# USBPD_Sink.net
KiCad netlist of a schematic drawn in Altium Designer
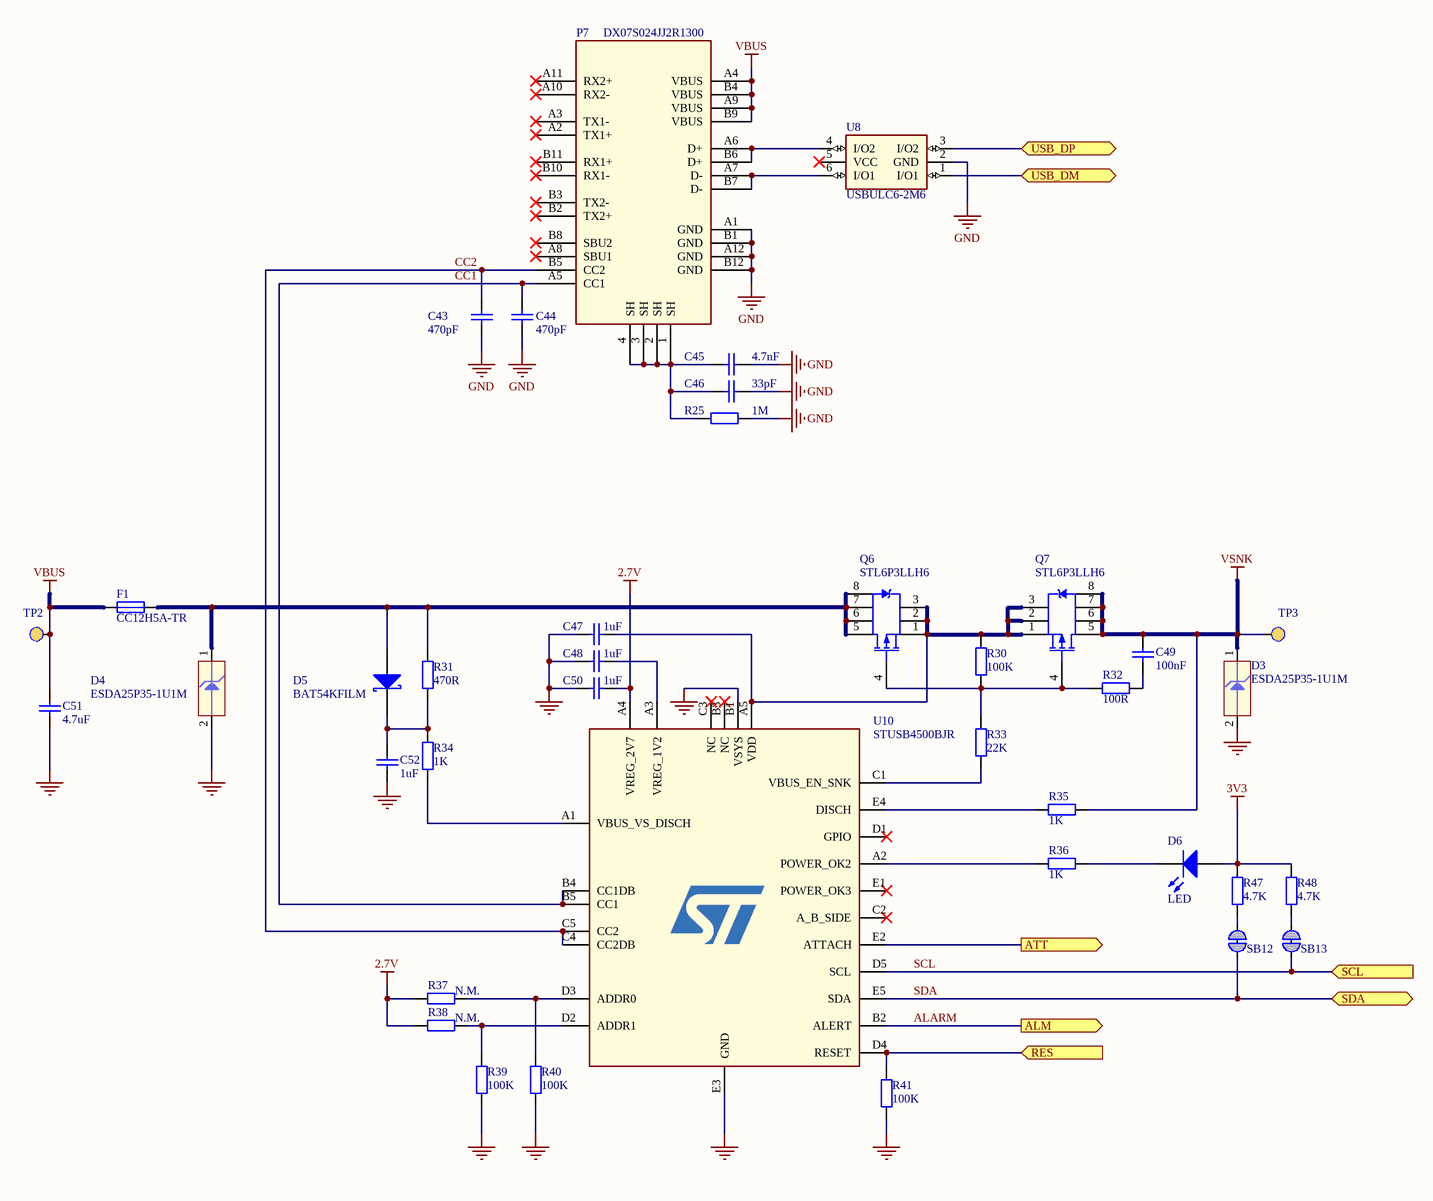
[diagram p0: USBPD_Sink.SchDoc]

(export (version "E")
  (design (tool "Eeschema 10.0.6"))
  (components
    (comp (ref "C43")
      (value "470pF")
      (footprint "C0402")
      (description "Capacitor (Semiconductor SIM Model)")
      (fields
        (field (name "MANUFACTURER") "Samsung EM")
        (field (name "MANUFACTURER PART NO.") "CL05C471JB5NNNC")
      )
      (libsource (lib "Miscellaneous Devices") (part "Cap Semi"))
    )
    (comp (ref "C44")
      (value "470pF")
      (footprint "C0402")
      (description "Capacitor (Semiconductor SIM Model)")
      (fields
        (field (name "MANUFACTURER") "Samsung EM")
        (field (name "MANUFACTURER PART NO.") "CL05C471JB5NNNC")
      )
      (libsource (lib "Miscellaneous Devices") (part "Cap Semi"))
    )
    (comp (ref "C45")
      (value "4.7nF")
      (footprint "C0402")
      (description "Capacitor (Semiconductor SIM Model)")
      (fields
        (field (name "MANUFACTURER") "YAGEO")
        (field (name "MANUFACTURER PART NO.") "CC0402KRX7R9BB472")
      )
      (libsource (lib "Miscellaneous Devices") (part "Cap Semi"))
    )
    (comp (ref "C46")
      (value "33pF")
      (footprint "C0402")
      (description "Capacitor (Semiconductor SIM Model)")
      (fields (field (name "MANUFACTURER") "AVX") (field (name "MANUFACTURER PART NO.") "04025A330JAT2A"))
      (libsource (lib "Miscellaneous Devices") (part "Cap Semi"))
    )
    (comp (ref "C47")
      (value "1uF")
      (footprint "C0402")
      (description "Capacitor (Semiconductor SIM Model)")
      (fields
        (field (name "MANUFACTURER") "muRata")
        (field (name "MANUFACTURER PART NO.") "GRM155R61E105KA12D")
      )
      (libsource (lib "Miscellaneous Devices") (part "Cap Semi"))
    )
    (comp (ref "C48")
      (value "1uF")
      (footprint "C0402")
      (description "Capacitor (Semiconductor SIM Model)")
      (fields
        (field (name "MANUFACTURER") "muRata")
        (field (name "MANUFACTURER PART NO.") "GRM155R61E105KA12D")
      )
      (libsource (lib "Miscellaneous Devices") (part "Cap Semi"))
    )
    (comp (ref "C49")
      (value "100nF")
      (footprint "C0402")
      (description "Capacitor (Semiconductor SIM Model)")
      (fields
        (field (name "MANUFACTURER") "YAGEO")
        (field (name "MANUFACTURER PART NO.") "CC0402KRX7R9BB104")
      )
      (libsource (lib "Miscellaneous Devices") (part "Cap Semi"))
    )
    (comp (ref "C50")
      (value "1uF")
      (footprint "C0402")
      (description "Capacitor (Semiconductor SIM Model)")
      (fields
        (field (name "MANUFACTURER") "muRata")
        (field (name "MANUFACTURER PART NO.") "GRM155R61E105KA12D")
      )
      (libsource (lib "Miscellaneous Devices") (part "Cap Semi"))
    )
    (comp (ref "C51")
      (value "4.7uF")
      (footprint "C0603")
      (description "Capacitor (Semiconductor SIM Model)")
      (fields
        (field (name "MANUFACTURER") "Samsung EM")
        (field (name "MANUFACTURER PART NO.") "CL10A475KA8NQNC")
      )
      (libsource (lib "Miscellaneous Devices") (part "Cap Semi"))
    )
    (comp (ref "C52")
      (value "1uF")
      (footprint "C0402")
      (description "Capacitor (Semiconductor SIM Model)")
      (fields
        (field (name "MANUFACTURER") "muRata")
        (field (name "MANUFACTURER PART NO.") "GRM155R61E105KA12D")
      )
      (libsource (lib "Miscellaneous Devices") (part "Cap Semi"))
    )
    (comp (ref "D3")
      (value "ESDA25P35-1U1M")
      (footprint "QFN1610")
      (description "ESD Diode Symbol")
      (fields (field (name "MANUFACTURER") "STMicroelectronics"))
      (libsource (lib "ESD_Diode") (part "ESD_Diode"))
    )
    (comp (ref "D4")
      (value "ESDA25P35-1U1M")
      (footprint "QFN1610")
      (description "ESD Diode Symbol")
      (fields (field (name "MANUFACTURER") "STMicroelectronics"))
      (libsource (lib "ESD_Diode") (part "ESD_Diode"))
    )
    (comp (ref "D5")
      (value "BAT54KFILM")
      (footprint "SOD-523")
      (description "Schottky Diode")
      (fields (field (name "MANUFACTURER") "STMicroelectronics"))
      (libsource (lib "Miscellaneous Devices") (part "D Schottky"))
    )
    (comp (ref "D6")
      (value "LED")
      (footprint "PICOLED")
      (description "Typical SMD LED")
      (fields
        (field (name "MANUFACTURER") "OSRAM")
        (field (name "MANUFACTURER PART NO.") "LTQH9G-Q2OO-25-2Z4Y-5-R18")
      )
      (libsource (lib "Miscellaneous Devices") (part "LED2"))
    )
    (comp (ref "F1")
      (value "CC12H5A-TR")
      (footprint "R1206")
      (description "Fuse")
      (fields (field (name "MANUFACTURER") "EATON"))
      (libsource (lib "DevKit_STM32L5") (part "Fuse"))
    )
    (comp (ref "P7")
      (value "DX07S024JJ2R1300")
      (footprint "DX07_USB_C")
      (description "24P USB C DUAL SMT ON BOARD")
      (fields (field (name "MANUFACTURER") "JAE"))
      (libsource (lib "DX07S024JJ2R1300") (part "DX07S024JJ2R1300"))
    )
    (comp (ref "Q6")
      (value "STL6P3LLH6")
      (footprint "PowerFLAT™ 3.3 x 3.3")
      (description "Power MOSFET")
      (fields (field (name "MANUFACTURER") "STMicroelectronics"))
      (libsource (lib "RUT_GE310_GNSS") (part "STL6P3LLH6"))
    )
    (comp (ref "Q7")
      (value "STL6P3LLH6")
      (footprint "PowerFLAT™ 3.3 x 3.3")
      (description "Power MOSFET")
      (fields (field (name "MANUFACTURER") "STMicroelectronics"))
      (libsource (lib "RUT_GE310_GNSS") (part "STL6P3LLH6"))
    )
    (comp (ref "R25")
      (value "1M")
      (footprint "R0402")
      (fields
        (field (name "MANUFACTURER") "ASJ")
        (field (name "MANUFACTURER PART NO.") "CR10-105-JK")
        (field (name "Comment") "Res2")
      )
      (libsource (lib "Miscellaneous Devices") (part "Res2"))
    )
    (comp (ref "R30")
      (value "100K")
      (footprint "R0402")
      (fields
        (field (name "MANUFACTURER") "ASJ")
        (field (name "MANUFACTURER PART NO.") "CR10-104-JN")
        (field (name "Comment") "Res2")
      )
      (libsource (lib "Miscellaneous Devices") (part "Res2"))
    )
    (comp (ref "R31")
      (value "470R")
      (footprint "R0402")
      (fields
        (field (name "MANUFACTURER") "ASJ")
        (field (name "MANUFACTURER PART NO.") "CR10-471-JK")
        (field (name "Comment") "Res2")
      )
      (libsource (lib "Miscellaneous Devices") (part "Res2"))
    )
    (comp (ref "R32")
      (value "100R")
      (footprint "R0402")
      (fields
        (field (name "MANUFACTURER") "YAGEO")
        (field (name "MANUFACTURER PART NO.") "RC0402JR-07100RL")
        (field (name "Comment") "Res2")
      )
      (libsource (lib "") (part "Res2_1"))
    )
    (comp (ref "R33")
      (value "22K")
      (footprint "R0402")
      (fields
        (field (name "MANUFACTURER") "ASJ")
        (field (name "MANUFACTURER PART NO.") "CR10-223-JK")
        (field (name "Comment") "Res2")
      )
      (libsource (lib "Miscellaneous Devices") (part "Res2"))
    )
    (comp (ref "R34")
      (value "1K")
      (footprint "R0402")
      (fields
        (field (name "MANUFACTURER") "ASJ")
        (field (name "MANUFACTURER PART NO.") "CR10-102-JK")
        (field (name "Comment") "Res2")
      )
      (libsource (lib "Miscellaneous Devices") (part "Res2"))
    )
    (comp (ref "R35")
      (value "1K")
      (footprint "R0402")
      (fields
        (field (name "MANUFACTURER") "ASJ")
        (field (name "MANUFACTURER PART NO.") "CR10-102-JK")
        (field (name "Comment") "Res2")
      )
      (libsource (lib "") (part "Res2_1"))
    )
    (comp (ref "R36")
      (value "1K")
      (footprint "R0402")
      (fields
        (field (name "MANUFACTURER") "ASJ")
        (field (name "MANUFACTURER PART NO.") "CR10-102-JK")
        (field (name "Comment") "Res2")
      )
      (libsource (lib "") (part "Res2_1"))
    )
    (comp (ref "R37")
      (value "N.M.")
      (footprint "R0402")
      (fields
        (field (name "MANUFACTURER") "Yageo")
        (field (name "MANUFACTURER PART NO.") "RC0402JR-0710KL")
        (field (name "Comment") "Res2")
      )
      (libsource (lib "") (part "Res2_1"))
    )
    (comp (ref "R38")
      (value "N.M.")
      (footprint "R0402")
      (fields
        (field (name "MANUFACTURER") "Yageo")
        (field (name "MANUFACTURER PART NO.") "RC0402JR-0710KL")
        (field (name "Comment") "Res2")
      )
      (libsource (lib "") (part "Res2_1"))
    )
    (comp (ref "R39")
      (value "100K")
      (footprint "R0402")
      (fields
        (field (name "MANUFACTURER") "ASJ")
        (field (name "MANUFACTURER PART NO.") "CR10-104-JN")
        (field (name "Comment") "Res2")
      )
      (libsource (lib "Miscellaneous Devices") (part "Res2"))
    )
    (comp (ref "R40")
      (value "100K")
      (footprint "R0402")
      (fields
        (field (name "MANUFACTURER") "ASJ")
        (field (name "MANUFACTURER PART NO.") "CR10-104-JN")
        (field (name "Comment") "Res2")
      )
      (libsource (lib "Miscellaneous Devices") (part "Res2"))
    )
    (comp (ref "R41")
      (value "100K")
      (footprint "R0402")
      (fields
        (field (name "MANUFACTURER") "ASJ")
        (field (name "MANUFACTURER PART NO.") "CR10-104-JN")
        (field (name "Comment") "Res2")
      )
      (libsource (lib "Miscellaneous Devices") (part "Res2"))
    )
    (comp (ref "R47")
      (value "4.7K")
      (footprint "R0402")
      (fields
        (field (name "MANUFACTURER") "ASJ")
        (field (name "MANUFACTURER PART NO.") "CR10-472-JK")
        (field (name "Comment") "Res2")
      )
      (libsource (lib "Miscellaneous Devices") (part "Res2"))
    )
    (comp (ref "R48")
      (value "4.7K")
      (footprint "R0402")
      (fields
        (field (name "MANUFACTURER") "ASJ")
        (field (name "MANUFACTURER PART NO.") "CR10-472-JK")
        (field (name "Comment") "Res2")
      )
      (libsource (lib "Miscellaneous Devices") (part "Res2"))
    )
    (comp (ref "SB12")
      (value "Solderbridge")
      (footprint "Solderbridge_Shorted")
      (libsource (lib "altium-import") (part "root_1_SOLDERBRIDGE_SHORTED_"))
    )
    (comp (ref "SB13")
      (value "Solderbridge")
      (footprint "Solderbridge_Shorted")
      (libsource (lib "altium-import") (part "root_1_SOLDERBRIDGE_SHORTED_"))
    )
    (comp (ref "TP2")
      (value "Test_Point")
      (footprint "TEST_POINT")
      (description "Test Point")
      (libsource (lib "Test Point") (part "Test_Point"))
    )
    (comp (ref "TP3")
      (value "Test_Point")
      (footprint "TEST_POINT")
      (description "Test Point")
      (libsource (lib "Test Point") (part "Test_Point"))
    )
    (comp (ref "U8")
      (value "USBULC6-2M6")
      (footprint "Micro_QFN_6L")
      (description "Ultra large bandwidth ESD protection")
      (fields (field (name "MANUFACTURER") "STMicroelectronics"))
      (libsource (lib "USBULC6-2M6") (part "USBULC6-2M6"))
    )
    (comp (ref "U10")
      (value "STUSB4500BJR")
      (footprint "WLCSP 2.6x2.6x0.5")
      (description "Standalone USB PD sink controller with short-to-VBUS protections")
      (fields (field (name "MANUFACTURER") "STMicroelectronics"))
      (libsource (lib "STUSB4500BJR ") (part "STUSB4500BJR"))
    )
  )
  (nets
    (net (code "1") (name "/ALARM") (class "Default")
      (node (ref "U10") (pin "B2") (pinfunction "ALERT_B2") (pintype "passive"))
    )
    (net (code "2") (name "/ATT") (class "Default")
      (node (ref "U10") (pin "E2") (pinfunction "ATTACH_E2") (pintype "passive"))
    )
    (net (code "3") (name "/CC1") (class "Default")
      (node (ref "C44") (pin "2") (pinfunction "2_2") (pintype "passive"))
      (node (ref "P7") (pin "A5") (pinfunction "CC1_A5") (pintype "passive"))
      (node (ref "U10") (pin "B4") (pinfunction "CC1DB_B4") (pintype "passive"))
      (node (ref "U10") (pin "B5") (pinfunction "CC1_B5") (pintype "passive"))
    )
    (net (code "4") (name "/CC2") (class "Default")
      (node (ref "C43") (pin "2") (pinfunction "2_2") (pintype "passive"))
      (node (ref "P7") (pin "B5") (pinfunction "CC2_B5") (pintype "passive"))
      (node (ref "U10") (pin "C4") (pinfunction "CC2DB_C4") (pintype "passive"))
      (node (ref "U10") (pin "C5") (pinfunction "CC2_C5") (pintype "passive"))
    )
    (net (code "5") (name "/RES") (class "Default")
      (node (ref "R41") (pin "1") (pinfunction "1_1") (pintype "passive"))
      (node (ref "U10") (pin "D4") (pinfunction "RESET_D4") (pintype "passive"))
    )
    (net (code "6") (name "/SCL") (class "Default")
      (node (ref "SB13") (pin "2") (pinfunction "1_2") (pintype "passive"))
      (node (ref "U10") (pin "D5") (pinfunction "SCL_D5") (pintype "passive"))
    )
    (net (code "7") (name "/SDA") (class "Default")
      (node (ref "SB12") (pin "2") (pinfunction "1_2") (pintype "passive"))
      (node (ref "U10") (pin "E5") (pinfunction "SDA_E5") (pintype "passive"))
    )
    (net (code "8") (name "/USB_DM") (class "Default")
      (node (ref "U8") (pin "1") (pinfunction "I/O1_1") (pintype "bidirectional"))
    )
    (net (code "9") (name "/USB_DP") (class "Default")
      (node (ref "U8") (pin "3") (pinfunction "I/O2_3") (pintype "bidirectional"))
    )
    (net (code "10") (name "2.7V") (class "Default")
      (node (ref "C50") (pin "1") (pinfunction "1_1") (pintype "passive"))
      (node (ref "R37") (pin "1") (pinfunction "1_1") (pintype "passive"))
      (node (ref "R38") (pin "1") (pinfunction "1_1") (pintype "passive"))
      (node (ref "U10") (pin "A4") (pinfunction "VREG_2V7_A4") (pintype "passive"))
    )
    (net (code "11") (name "3V3") (class "Default")
      (node (ref "D6") (pin "1") (pinfunction "A_1") (pintype "passive"))
      (node (ref "R47") (pin "1") (pinfunction "1_1") (pintype "passive"))
      (node (ref "R48") (pin "1") (pinfunction "1_1") (pintype "passive"))
    )
    (net (code "12") (name "GND") (class "Default")
      (node (ref "C43") (pin "1") (pinfunction "1_1") (pintype "passive"))
      (node (ref "C44") (pin "1") (pinfunction "1_1") (pintype "passive"))
      (node (ref "C45") (pin "1") (pinfunction "1_1") (pintype "passive"))
      (node (ref "C46") (pin "1") (pinfunction "1_1") (pintype "passive"))
      (node (ref "C47") (pin "2") (pinfunction "2_2") (pintype "passive"))
      (node (ref "C48") (pin "2") (pinfunction "2_2") (pintype "passive"))
      (node (ref "C50") (pin "2") (pinfunction "2_2") (pintype "passive"))
      (node (ref "C51") (pin "2") (pinfunction "2_2") (pintype "passive"))
      (node (ref "C52") (pin "2") (pinfunction "2_2") (pintype "passive"))
      (node (ref "D3") (pin "2") (pinfunction "PIN2_2") (pintype "passive"))
      (node (ref "D4") (pin "2") (pinfunction "PIN2_2") (pintype "passive"))
      (node (ref "P7") (pin "A1") (pinfunction "GND_A1") (pintype "passive"))
      (node (ref "P7") (pin "A12") (pinfunction "GND_A12") (pintype "passive"))
      (node (ref "P7") (pin "B1") (pinfunction "GND_B1") (pintype "passive"))
      (node (ref "P7") (pin "B12") (pinfunction "GND_B12") (pintype "passive"))
      (node (ref "R25") (pin "1") (pinfunction "1_1") (pintype "passive"))
      (node (ref "R39") (pin "2") (pinfunction "2_2") (pintype "passive"))
      (node (ref "R40") (pin "2") (pinfunction "2_2") (pintype "passive"))
      (node (ref "R41") (pin "2") (pinfunction "2_2") (pintype "passive"))
      (node (ref "U10") (pin "B1") (pinfunction "VSYS_B1") (pintype "passive"))
      (node (ref "U10") (pin "E3") (pinfunction "GND_E3") (pintype "passive"))
      (node (ref "U8") (pin "2") (pinfunction "GND_2") (pintype "power_in"))
    )
    (net (code "13") (name "Net-(C45-Pad2)") (class "Default")
      (node (ref "C45") (pin "2") (pinfunction "2_2") (pintype "passive"))
      (node (ref "C46") (pin "2") (pinfunction "2_2") (pintype "passive"))
      (node (ref "P7") (pin "1") (pinfunction "SH_1") (pintype "passive"))
      (node (ref "P7") (pin "2") (pinfunction "SH_2") (pintype "passive"))
      (node (ref "P7") (pin "3") (pinfunction "SH_3") (pintype "passive"))
      (node (ref "P7") (pin "4") (pinfunction "SH_4") (pintype "passive"))
      (node (ref "R25") (pin "2") (pinfunction "2_2") (pintype "passive"))
    )
    (net (code "14") (name "Net-(C49-Pad1)") (class "Default")
      (node (ref "C49") (pin "1") (pinfunction "1_1") (pintype "passive"))
      (node (ref "R32") (pin "2") (pinfunction "2_2") (pintype "passive"))
    )
    (net (code "15") (name "Net-(D4-PIN1)") (class "Default")
      (node (ref "D4") (pin "1") (pinfunction "PIN1_1") (pintype "passive"))
      (node (ref "D5") (pin "1") (pinfunction "A_1") (pintype "passive"))
      (node (ref "F1") (pin "1") (pinfunction "1_1") (pintype "passive"))
      (node (ref "Q6") (pin "5") (pinfunction "D_5") (pintype "passive"))
      (node (ref "Q6") (pin "6") (pinfunction "D_6") (pintype "passive"))
      (node (ref "Q6") (pin "7") (pinfunction "D_7") (pintype "passive"))
      (node (ref "Q6") (pin "8") (pinfunction "D_8") (pintype "passive"))
      (node (ref "R31") (pin "1") (pinfunction "1_1") (pintype "passive"))
    )
    (net (code "16") (name "Net-(D5-K)") (class "Default")
      (node (ref "C52") (pin "1") (pinfunction "1_1") (pintype "passive"))
      (node (ref "D5") (pin "2") (pinfunction "K_2") (pintype "passive"))
      (node (ref "R31") (pin "2") (pinfunction "2_2") (pintype "passive"))
      (node (ref "R34") (pin "1") (pinfunction "1_1") (pintype "passive"))
    )
    (net (code "17") (name "Net-(D6-K)") (class "Default")
      (node (ref "D6") (pin "2") (pinfunction "K_2") (pintype "passive"))
      (node (ref "R36") (pin "2") (pinfunction "2_2") (pintype "passive"))
    )
    (net (code "18") (name "Net-(P7-D+-PadA6)") (class "Default")
      (node (ref "P7") (pin "A6") (pinfunction "D+_A6") (pintype "passive"))
      (node (ref "P7") (pin "B6") (pinfunction "D+_B6") (pintype "passive"))
      (node (ref "U8") (pin "4") (pinfunction "I/O2_4") (pintype "bidirectional"))
    )
    (net (code "19") (name "Net-(P7-D--PadA7)") (class "Default")
      (node (ref "P7") (pin "A7") (pinfunction "D-_A7") (pintype "passive"))
      (node (ref "P7") (pin "B7") (pinfunction "D-_B7") (pintype "passive"))
      (node (ref "U8") (pin "6") (pinfunction "I/O1_6") (pintype "bidirectional"))
    )
    (net (code "20") (name "Net-(Q6-G)") (class "Default")
      (node (ref "Q6") (pin "4") (pinfunction "G_4") (pintype "passive"))
      (node (ref "Q7") (pin "4") (pinfunction "G_4") (pintype "passive"))
      (node (ref "R30") (pin "2") (pinfunction "2_2") (pintype "passive"))
      (node (ref "R32") (pin "1") (pinfunction "1_1") (pintype "passive"))
      (node (ref "R33") (pin "1") (pinfunction "1_1") (pintype "passive"))
    )
    (net (code "21") (name "Net-(SB12-0)") (class "Default")
      (node (ref "R47") (pin "2") (pinfunction "2_2") (pintype "passive"))
      (node (ref "SB12") (pin "1") (pinfunction "0_1") (pintype "passive"))
    )
    (net (code "22") (name "Net-(SB13-0)") (class "Default")
      (node (ref "R48") (pin "2") (pinfunction "2_2") (pintype "passive"))
      (node (ref "SB13") (pin "1") (pinfunction "0_1") (pintype "passive"))
    )
    (net (code "23") (name "Net-(U10-ADDR0)") (class "Default")
      (node (ref "R37") (pin "2") (pinfunction "2_2") (pintype "passive"))
      (node (ref "R40") (pin "1") (pinfunction "1_1") (pintype "passive"))
      (node (ref "U10") (pin "D3") (pinfunction "ADDR0_D3") (pintype "passive"))
    )
    (net (code "24") (name "Net-(U10-ADDR1)") (class "Default")
      (node (ref "R38") (pin "2") (pinfunction "2_2") (pintype "passive"))
      (node (ref "R39") (pin "1") (pinfunction "1_1") (pintype "passive"))
      (node (ref "U10") (pin "D2") (pinfunction "ADDR1_D2") (pintype "passive"))
    )
    (net (code "25") (name "Net-(U10-DISCH)") (class "Default")
      (node (ref "R35") (pin "1") (pinfunction "1_1") (pintype "passive"))
      (node (ref "U10") (pin "E4") (pinfunction "DISCH_E4") (pintype "passive"))
    )
    (net (code "26") (name "Net-(U10-POWER_OK2)") (class "Default")
      (node (ref "R36") (pin "1") (pinfunction "1_1") (pintype "passive"))
      (node (ref "U10") (pin "A2") (pinfunction "POWER_OK2_A2") (pintype "passive"))
    )
    (net (code "27") (name "Net-(U10-VBUS_EN_SNK)") (class "Default")
      (node (ref "R33") (pin "2") (pinfunction "2_2") (pintype "passive"))
      (node (ref "U10") (pin "C1") (pinfunction "VBUS_EN_SNK_C1") (pintype "passive"))
    )
    (net (code "28") (name "Net-(U10-VBUS_VS_DISCH)") (class "Default")
      (node (ref "R34") (pin "2") (pinfunction "2_2") (pintype "passive"))
      (node (ref "U10") (pin "A1") (pinfunction "VBUS_VS_DISCH_A1") (pintype "passive"))
    )
    (net (code "29") (name "Net-(U10-VDD)") (class "Default")
      (node (ref "C47") (pin "1") (pinfunction "1_1") (pintype "passive"))
      (node (ref "Q6") (pin "1") (pinfunction "S_1") (pintype "passive"))
      (node (ref "Q6") (pin "2") (pinfunction "S_2") (pintype "passive"))
      (node (ref "Q6") (pin "3") (pinfunction "S_3") (pintype "passive"))
      (node (ref "Q7") (pin "1") (pinfunction "S_1") (pintype "passive"))
      (node (ref "Q7") (pin "2") (pinfunction "S_2") (pintype "passive"))
      (node (ref "Q7") (pin "3") (pinfunction "S_3") (pintype "passive"))
      (node (ref "R30") (pin "1") (pinfunction "1_1") (pintype "passive"))
      (node (ref "U10") (pin "A5") (pinfunction "VDD_A5") (pintype "passive"))
    )
    (net (code "30") (name "Net-(U10-VREG_1V2)") (class "Default")
      (node (ref "C48") (pin "1") (pinfunction "1_1") (pintype "passive"))
      (node (ref "U10") (pin "A3") (pinfunction "VREG_1V2_A3") (pintype "passive"))
    )
    (net (code "31") (name "VBUS") (class "Default")
      (node (ref "C51") (pin "1") (pinfunction "1_1") (pintype "passive"))
      (node (ref "F1") (pin "2") (pinfunction "2_2") (pintype "passive"))
      (node (ref "P7") (pin "A4") (pinfunction "VBUS_A4") (pintype "passive"))
      (node (ref "P7") (pin "A9") (pinfunction "VBUS_A9") (pintype "passive"))
      (node (ref "P7") (pin "B4") (pinfunction "VBUS_B4") (pintype "passive"))
      (node (ref "P7") (pin "B9") (pinfunction "VBUS_B9") (pintype "passive"))
      (node (ref "TP2") (pin "0") (pinfunction "0_0") (pintype "passive"))
    )
    (net (code "32") (name "VSNK") (class "Default")
      (node (ref "C49") (pin "2") (pinfunction "2_2") (pintype "passive"))
      (node (ref "D3") (pin "1") (pinfunction "PIN1_1") (pintype "passive"))
      (node (ref "Q7") (pin "5") (pinfunction "D_5") (pintype "passive"))
      (node (ref "Q7") (pin "6") (pinfunction "D_6") (pintype "passive"))
      (node (ref "Q7") (pin "7") (pinfunction "D_7") (pintype "passive"))
      (node (ref "Q7") (pin "8") (pinfunction "D_8") (pintype "passive"))
      (node (ref "R35") (pin "2") (pinfunction "2_2") (pintype "passive"))
      (node (ref "TP3") (pin "0") (pinfunction "0_0") (pintype "passive"))
    )
    (net (code "33") (name "unconnected-(P7-RX1+-PadB11)") (class "Default")
      (node (ref "P7") (pin "B11") (pinfunction "RX1+_B11") (pintype "passive+no_connect"))
    )
    (net (code "34") (name "unconnected-(P7-RX1--PadB10)") (class "Default")
      (node (ref "P7") (pin "B10") (pinfunction "RX1-_B10") (pintype "passive+no_connect"))
    )
    (net (code "35") (name "unconnected-(P7-RX2+-PadA11)") (class "Default")
      (node (ref "P7") (pin "A11") (pinfunction "RX2+_A11") (pintype "passive+no_connect"))
    )
    (net (code "36") (name "unconnected-(P7-RX2--PadA10)") (class "Default")
      (node (ref "P7") (pin "A10") (pinfunction "RX2-_A10") (pintype "passive+no_connect"))
    )
    (net (code "37") (name "unconnected-(P7-SBU1-PadA8)") (class "Default")
      (node (ref "P7") (pin "A8") (pinfunction "SBU1_A8") (pintype "passive+no_connect"))
    )
    (net (code "38") (name "unconnected-(P7-SBU2-PadB8)") (class "Default")
      (node (ref "P7") (pin "B8") (pinfunction "SBU2_B8") (pintype "passive+no_connect"))
    )
    (net (code "39") (name "unconnected-(P7-TX1+-PadA2)") (class "Default")
      (node (ref "P7") (pin "A2") (pinfunction "TX1+_A2") (pintype "passive+no_connect"))
    )
    (net (code "40") (name "unconnected-(P7-TX1--PadA3)") (class "Default")
      (node (ref "P7") (pin "A3") (pinfunction "TX1-_A3") (pintype "passive+no_connect"))
    )
    (net (code "41") (name "unconnected-(P7-TX2+-PadB2)") (class "Default")
      (node (ref "P7") (pin "B2") (pinfunction "TX2+_B2") (pintype "passive+no_connect"))
    )
    (net (code "42") (name "unconnected-(P7-TX2--PadB3)") (class "Default")
      (node (ref "P7") (pin "B3") (pinfunction "TX2-_B3") (pintype "passive+no_connect"))
    )
    (net (code "43") (name "unconnected-(U8-VCC-Pad5)") (class "Default")
      (node (ref "U8") (pin "5") (pinfunction "VCC_5") (pintype "power_in+no_connect"))
    )
    (net (code "44") (name "unconnected-(U10-A_B_SIDE-PadC2)") (class "Default")
      (node (ref "U10") (pin "C2") (pinfunction "A_B_SIDE_C2") (pintype "passive+no_connect"))
    )
    (net (code "45") (name "unconnected-(U10-GPIO-PadD1)") (class "Default")
      (node (ref "U10") (pin "D1") (pinfunction "GPIO_D1") (pintype "passive+no_connect"))
    )
    (net (code "46") (name "unconnected-(U10-NC-PadB3)") (class "Default")
      (node (ref "U10") (pin "B3") (pinfunction "NC_B3") (pintype "passive+no_connect"))
    )
    (net (code "47") (name "unconnected-(U10-NC-PadC3)") (class "Default")
      (node (ref "U10") (pin "C3") (pinfunction "NC_C3") (pintype "passive+no_connect"))
    )
    (net (code "48") (name "unconnected-(U10-POWER_OK3-PadE1)") (class "Default")
      (node (ref "U10") (pin "E1") (pinfunction "POWER_OK3_E1") (pintype "passive+no_connect"))
    )
  )
)
